# bt_relay2.net
KiCad netlist of a schematic drawn in EAGLE
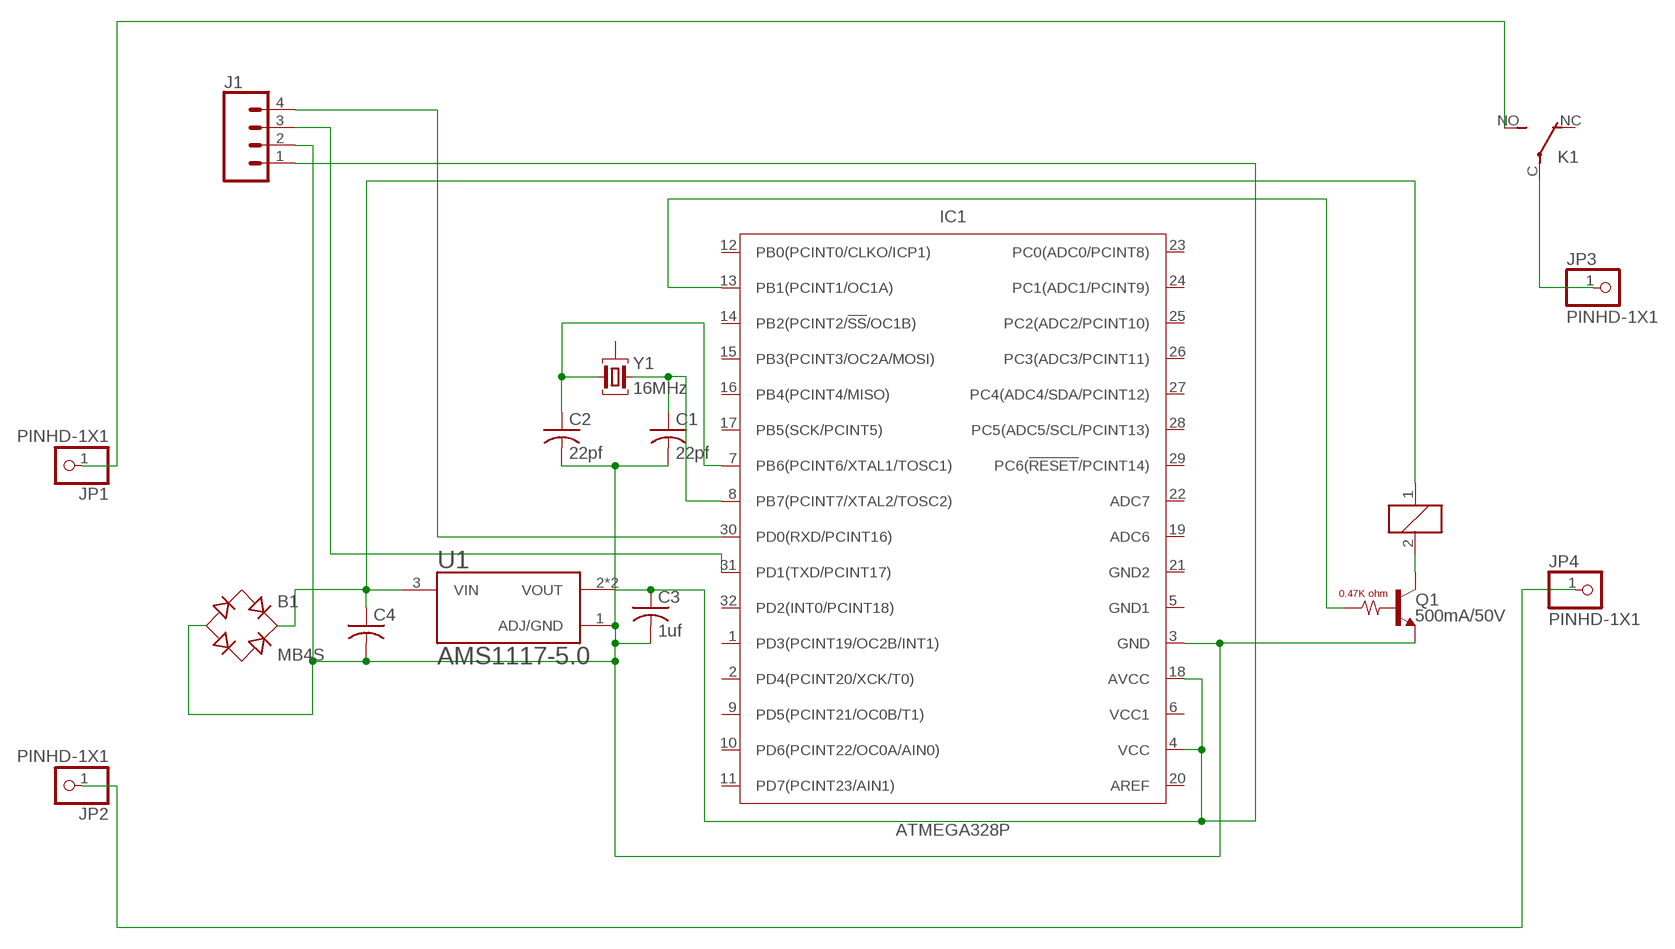
[diagram p0: schematic, sheet 1]

(export (version "E")
  (design (tool "Eeschema 10.0.6"))
  (components
    (comp (ref "B1")
      (value "MB4S")
      (footprint "eagle-import:SOIC-4")
      (libsource (lib "eagle-import") (part "MBS4"))
    )
    (comp (ref "C1")
      (value "22pf")
      (footprint "eagle-import:C0402")
      (libsource (lib "eagle-import") (part "C-USC0402"))
    )
    (comp (ref "C2")
      (value "22pf")
      (footprint "eagle-import:C0402")
      (libsource (lib "eagle-import") (part "C-USC0402"))
    )
    (comp (ref "C3")
      (value "1uf")
      (footprint "eagle-import:C0402")
      (libsource (lib "eagle-import") (part "C-USC0402"))
    )
    (comp (ref "C4")
      (value "C-USC0402")
      (footprint "eagle-import:C0402")
      (libsource (lib "eagle-import") (part "C-USC0402"))
    )
    (comp (ref "IC1")
      (value "ATMEGA328P")
      (footprint "eagle-import:QFN50P500X500X90-33T310N")
      (fields (field (name "MANUFACTURER") "Microchip") (field (name "MPN") "ATmega328P-AU"))
      (libsource (lib "eagle-import") (part "ATMEGA328P_VQFN"))
    )
    (comp (ref "J1")
      (value "CONN_04")
      (footprint "eagle-import:1X04")
      (libsource (lib "eagle-import") (part "CONN_04"))
    )
    (comp (ref "JP1")
      (value "PINHD-1X1")
      (footprint "eagle-import:1X01")
      (libsource (lib "eagle-import") (part "PINHD-1X1"))
    )
    (comp (ref "JP2")
      (value "PINHD-1X1")
      (footprint "eagle-import:1X01")
      (libsource (lib "eagle-import") (part "PINHD-1X1"))
    )
    (comp (ref "JP3")
      (value "PINHD-1X1")
      (footprint "eagle-import:1X01")
      (libsource (lib "eagle-import") (part "PINHD-1X1"))
    )
    (comp (ref "JP4")
      (value "PINHD-1X1")
      (footprint "eagle-import:1X01")
      (libsource (lib "eagle-import") (part "PINHD-1X1"))
    )
    (comp (ref "K1")
      (value "CP1SA-12V")
      (footprint "eagle-import:CP1SA")
      (fields (field (name "MPN") "CP1SA-12V-X"))
      (libsource (lib "eagle-import") (part "CP1?-SA12V"))
    )
    (comp (ref "Q1")
      (value "500mA/50V")
      (footprint "eagle-import:SOT23-3")
      (libsource (lib "eagle-import") (part "TRANS_NPN_RES-DDTD142TC-7-F"))
    )
    (comp (ref "U1")
      (value "AMS1117-5.0")
      (footprint "eagle-import:SOT229P700X180-4N")
      (fields (field (name "MF") "Advanced Monolithic Systems"))
      (libsource (lib "eagle-import") (part "AMS1117-5.0"))
    )
    (comp (ref "Y1")
      (value "16MHz")
      (footprint "eagle-import:CRYSTAL_CMR200TB")
      (libsource (lib "eagle-import") (part "CRYSTAL_CMR200TB"))
    )
  )
  (nets
    (net (code "1") (name "/AREF") (class "Default")
      (node (ref "IC1") (pin "20") (pinfunction "AREF_20") (pintype "power_in"))
    )
    (net (code "2") (name "/VCC1") (class "Default")
      (node (ref "IC1") (pin "6") (pinfunction "VCC1_6") (pintype "power_in"))
    )
    (net (code "3") (name "Net-(IC1-AVCC)") (class "Default")
      (node (ref "C3") (pin "1") (pinfunction "1_1") (pintype "passive"))
      (node (ref "IC1") (pin "18") (pinfunction "AVCC_18") (pintype "power_in"))
      (node (ref "IC1") (pin "4") (pinfunction "VCC_4") (pintype "power_in"))
      (node (ref "J1") (pin "1") (pinfunction "1_1") (pintype "passive"))
      (node (ref "U1") (pin "2") (pinfunction "VOUT_2") (pintype "output"))
      (node (ref "U1") (pin "4") (pinfunction "VOUT_4") (pintype "output"))
    )
    (net (code "4") (name "Net-(IC1-GND)") (class "Default")
      (node (ref "B1") (pin "-") (pinfunction "-_-") (pintype "passive"))
      (node (ref "C1") (pin "2") (pinfunction "2_2") (pintype "passive"))
      (node (ref "C2") (pin "2") (pinfunction "2_2") (pintype "passive"))
      (node (ref "C3") (pin "2") (pinfunction "2_2") (pintype "passive"))
      (node (ref "C4") (pin "2") (pinfunction "2_2") (pintype "passive"))
      (node (ref "IC1") (pin "3") (pinfunction "GND_3") (pintype "passive"))
      (node (ref "J1") (pin "2") (pinfunction "2_2") (pintype "passive"))
      (node (ref "Q1") (pin "2") (pinfunction "E_2") (pintype "passive"))
      (node (ref "U1") (pin "1") (pinfunction "ADJ/GND_1") (pintype "power_in"))
    )
    (net (code "5") (name "Net-(IC1-PB1(PCINT1{slash}OC1A))") (class "Default")
      (node (ref "IC1") (pin "13") (pinfunction "PB1(PCINT1/OC1A)_13") (pintype "bidirectional"))
      (node (ref "Q1") (pin "1") (pinfunction "B_1") (pintype "passive"))
    )
    (net (code "6") (name "Net-(IC1-PB6(PCINT6{slash}XTAL1{slash}TOSC1))") (class "Default")
      (node (ref "C2") (pin "1") (pinfunction "1_1") (pintype "passive"))
      (node (ref "IC1") (pin "7") (pinfunction "PB6(PCINT6/XTAL1/TOSC1)_7") (pintype "input"))
      (node (ref "Y1") (pin "1") (pinfunction "1_1") (pintype "passive"))
    )
    (net (code "7") (name "Net-(IC1-PB7(PCINT7{slash}XTAL2{slash}TOSC2))") (class "Default")
      (node (ref "C1") (pin "1") (pinfunction "1_1") (pintype "passive"))
      (node (ref "IC1") (pin "8") (pinfunction "PB7(PCINT7/XTAL2/TOSC2)_8") (pintype "input"))
      (node (ref "Y1") (pin "2") (pinfunction "2_2") (pintype "passive"))
    )
    (net (code "8") (name "Net-(IC1-PD0(RXD{slash}PCINT16))") (class "Default")
      (node (ref "IC1") (pin "30") (pinfunction "PD0(RXD/PCINT16)_30") (pintype "bidirectional"))
      (node (ref "J1") (pin "4") (pinfunction "4_4") (pintype "passive"))
    )
    (net (code "9") (name "Net-(IC1-PD1(TXD{slash}PCINT17))") (class "Default")
      (node (ref "IC1") (pin "31") (pinfunction "PD1(TXD/PCINT17)_31") (pintype "bidirectional"))
      (node (ref "J1") (pin "3") (pinfunction "3_3") (pintype "passive"))
    )
    (net (code "10") (name "Net-(JP2-Pad1)") (class "Default")
      (node (ref "JP2") (pin "1") (pinfunction "1_1") (pintype "passive"))
      (node (ref "JP4") (pin "1") (pinfunction "1_1") (pintype "passive"))
    )
    (net (code "11") (name "Net-(K1B-P)") (class "Default")
      (node (ref "JP3") (pin "1") (pinfunction "1_1") (pintype "passive"))
      (node (ref "K1") (pin "C") (pinfunction "P_C") (pintype "passive"))
    )
    (net (code "12") (name "Net-(K1B-S)") (class "Default")
      (node (ref "JP1") (pin "1") (pinfunction "1_1") (pintype "passive"))
      (node (ref "K1") (pin "NO") (pinfunction "S_NO") (pintype "passive"))
    )
    (net (code "13") (name "Net-(Q1-C)") (class "Default")
      (node (ref "K1") (pin "2") (pinfunction "2_2") (pintype "passive"))
      (node (ref "Q1") (pin "3") (pinfunction "C_3") (pintype "passive"))
    )
    (net (code "14") (name "Net-(U1-VIN)") (class "Default")
      (node (ref "B1") (pin "+") (pinfunction "+_+") (pintype "passive"))
      (node (ref "C4") (pin "1") (pinfunction "1_1") (pintype "passive"))
      (node (ref "K1") (pin "1") (pinfunction "1_1") (pintype "passive"))
      (node (ref "U1") (pin "3") (pinfunction "VIN_3") (pintype "input"))
    )
    (net (code "15") (name "unconnected-(B1-AC1-Pad~1)") (class "Default")
      (node (ref "B1") (pin "~1") (pinfunction "AC1_~1") (pintype "passive"))
    )
    (net (code "16") (name "unconnected-(B1-AC2-Pad~2)") (class "Default")
      (node (ref "B1") (pin "~2") (pinfunction "AC2_~2") (pintype "passive"))
    )
    (net (code "17") (name "unconnected-(IC1-ADC6-Pad19)") (class "Default")
      (node (ref "IC1") (pin "19") (pinfunction "ADC6_19") (pintype "bidirectional"))
    )
    (net (code "18") (name "unconnected-(IC1-ADC7-Pad22)") (class "Default")
      (node (ref "IC1") (pin "22") (pinfunction "ADC7_22") (pintype "bidirectional"))
    )
    (net (code "19") (name "unconnected-(IC1-GND1-Pad5)") (class "Default")
      (node (ref "IC1") (pin "5") (pinfunction "GND1_5") (pintype "passive"))
    )
    (net (code "20") (name "unconnected-(IC1-GND2-Pad21)") (class "Default")
      (node (ref "IC1") (pin "21") (pinfunction "GND2_21") (pintype "passive"))
    )
    (net (code "21") (name "unconnected-(IC1-PB0(PCINT0{slash}CLKO{slash}ICP1)-Pad12)") (class "Default")
      (node (ref "IC1") (pin "12") (pinfunction "PB0(PCINT0/CLKO/ICP1)_12") (pintype "bidirectional"))
    )
    (net (code "22") (name "unconnected-(IC1-PB2(PCINT2{slash}~{SS}{slash}OC1B)-Pad14)") (class "Default")
      (node (ref "IC1") (pin "14") (pinfunction "PB2(PCINT2/~{SS}/OC1B)_14") (pintype "bidirectional"))
    )
    (net (code "23") (name "unconnected-(IC1-PB3(PCINT3{slash}OC2A{slash}MOSI)-Pad15)") (class "Default")
      (node (ref "IC1") (pin "15") (pinfunction "PB3(PCINT3/OC2A/MOSI)_15") (pintype "bidirectional"))
    )
    (net (code "24") (name "unconnected-(IC1-PB4(PCINT4{slash}MISO)-Pad16)") (class "Default")
      (node (ref "IC1") (pin "16") (pinfunction "PB4(PCINT4/MISO)_16") (pintype "bidirectional"))
    )
    (net (code "25") (name "unconnected-(IC1-PB5(SCK{slash}PCINT5)-Pad17)") (class "Default")
      (node (ref "IC1") (pin "17") (pinfunction "PB5(SCK/PCINT5)_17") (pintype "bidirectional"))
    )
    (net (code "26") (name "unconnected-(IC1-PC0(ADC0{slash}PCINT8)-Pad23)") (class "Default")
      (node (ref "IC1") (pin "23") (pinfunction "PC0(ADC0/PCINT8)_23") (pintype "bidirectional"))
    )
    (net (code "27") (name "unconnected-(IC1-PC1(ADC1{slash}PCINT9)-Pad24)") (class "Default")
      (node (ref "IC1") (pin "24") (pinfunction "PC1(ADC1/PCINT9)_24") (pintype "bidirectional"))
    )
    (net (code "28") (name "unconnected-(IC1-PC2(ADC2{slash}PCINT10)-Pad25)") (class "Default")
      (node (ref "IC1") (pin "25") (pinfunction "PC2(ADC2/PCINT10)_25") (pintype "bidirectional"))
    )
    (net (code "29") (name "unconnected-(IC1-PC3(ADC3{slash}PCINT11)-Pad26)") (class "Default")
      (node (ref "IC1") (pin "26") (pinfunction "PC3(ADC3/PCINT11)_26") (pintype "bidirectional"))
    )
    (net (code "30") (name "unconnected-(IC1-PC4(ADC4{slash}SDA{slash}PCINT12)-Pad27)") (class "Default")
      (node (ref "IC1") (pin "27") (pinfunction "PC4(ADC4/SDA/PCINT12)_27") (pintype "bidirectional"))
    )
    (net (code "31") (name "unconnected-(IC1-PC5(ADC5{slash}SCL{slash}PCINT13)-Pad28)") (class "Default")
      (node (ref "IC1") (pin "28") (pinfunction "PC5(ADC5/SCL/PCINT13)_28") (pintype "bidirectional"))
    )
    (net (code "32") (name "unconnected-(IC1-PC6(~{RESET}{slash}PCINT14)-Pad29)") (class "Default")
      (node (ref "IC1") (pin "29") (pinfunction "PC6(~{RESET}/PCINT14)_29") (pintype "bidirectional"))
    )
    (net (code "33") (name "unconnected-(IC1-PD2(INT0{slash}PCINT18)-Pad32)") (class "Default")
      (node (ref "IC1") (pin "32") (pinfunction "PD2(INT0/PCINT18)_32") (pintype "bidirectional"))
    )
    (net (code "34") (name "unconnected-(IC1-PD3(PCINT19{slash}OC2B{slash}INT1)-Pad1)") (class "Default")
      (node (ref "IC1") (pin "1") (pinfunction "PD3(PCINT19/OC2B/INT1)_1") (pintype "bidirectional"))
    )
    (net (code "35") (name "unconnected-(IC1-PD4(PCINT20{slash}XCK{slash}T0)-Pad2)") (class "Default")
      (node (ref "IC1") (pin "2") (pinfunction "PD4(PCINT20/XCK/T0)_2") (pintype "bidirectional"))
    )
    (net (code "36") (name "unconnected-(IC1-PD5(PCINT21{slash}OC0B{slash}T1)-Pad9)") (class "Default")
      (node (ref "IC1") (pin "9") (pinfunction "PD5(PCINT21/OC0B/T1)_9") (pintype "bidirectional"))
    )
    (net (code "37") (name "unconnected-(IC1-PD6(PCINT22{slash}OC0A{slash}AIN0)-Pad10)") (class "Default")
      (node (ref "IC1") (pin "10") (pinfunction "PD6(PCINT22/OC0A/AIN0)_10") (pintype "bidirectional"))
    )
    (net (code "38") (name "unconnected-(IC1-PD7(PCINT23{slash}AIN1)-Pad11)") (class "Default")
      (node (ref "IC1") (pin "11") (pinfunction "PD7(PCINT23/AIN1)_11") (pintype "bidirectional"))
    )
    (net (code "39") (name "unconnected-(K1B-O-PadNC)") (class "Default")
      (node (ref "K1") (pin "NC") (pinfunction "O_NC") (pintype "passive"))
    )
    (net (code "40") (name "unconnected-(Y1-G-Pad3)") (class "Default")
      (node (ref "Y1") (pin "3") (pinfunction "G_3") (pintype "passive"))
    )
  )
)
